# Adafruit_VS1053_Headphone_FeatherWing.net
KiCad netlist of a schematic drawn in EAGLE
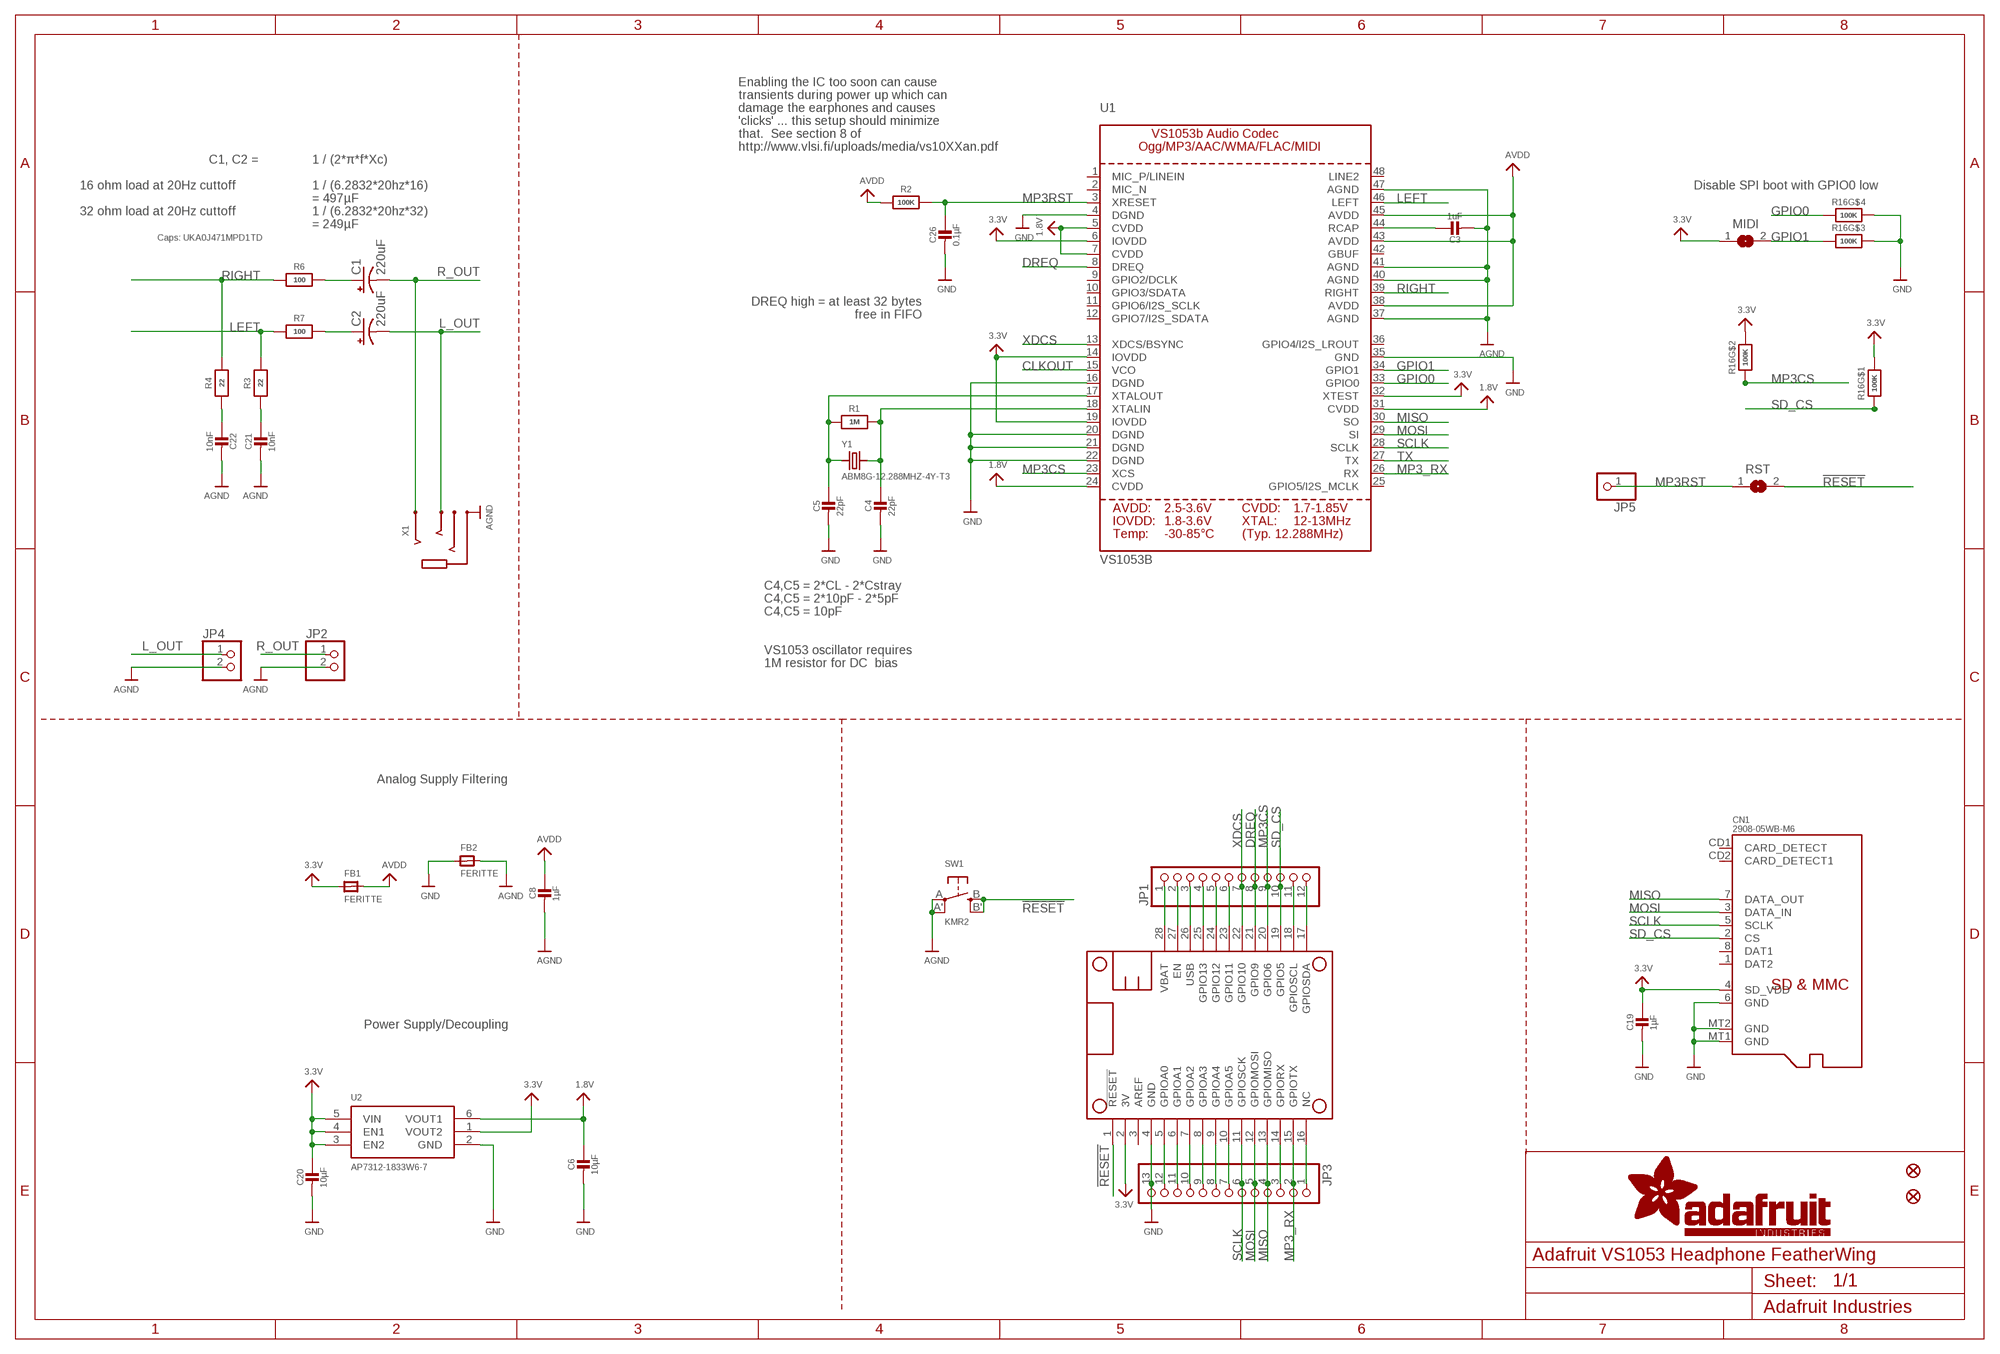
[diagram p0: schematic, sheet 1]

(export (version "E")
  (design (tool "Eeschema 10.0.6"))
  (components
    (comp (ref "C1")
      (value "220uF")
      (footprint "eagle-import:PANASONIC_C")
      (libsource (lib "eagle-import") (part "CPOL-USC"))
    )
    (comp (ref "C2")
      (value "220uF")
      (footprint "eagle-import:PANASONIC_C")
      (libsource (lib "eagle-import") (part "CPOL-USC"))
    )
    (comp (ref "C3")
      (value "1uF")
      (footprint "eagle-import:0603-NO")
      (libsource (lib "eagle-import") (part "CAP_CERAMIC0603_NO"))
    )
    (comp (ref "C4")
      (value "22pF")
      (footprint "eagle-import:0603-NO")
      (libsource (lib "eagle-import") (part "CAP_CERAMIC0603_NO"))
    )
    (comp (ref "C5")
      (value "22pF")
      (footprint "eagle-import:0603-NO")
      (libsource (lib "eagle-import") (part "CAP_CERAMIC0603_NO"))
    )
    (comp (ref "C6")
      (value "10µF")
      (footprint "eagle-import:_0805MP")
      (libsource (lib "eagle-import") (part "CAP_CERAMIC_0805MP"))
    )
    (comp (ref "C8")
      (value "1µF")
      (footprint "eagle-import:0603-NO")
      (libsource (lib "eagle-import") (part "CAP_CERAMIC0603_NO"))
    )
    (comp (ref "C19")
      (value "1µF")
      (footprint "eagle-import:0603-NO")
      (libsource (lib "eagle-import") (part "CAP_CERAMIC0603_NO"))
    )
    (comp (ref "C20")
      (value "10µF")
      (footprint "eagle-import:0805-NO")
      (libsource (lib "eagle-import") (part "CAP_CERAMIC0805-NOOUTLINE"))
    )
    (comp (ref "C21")
      (value "10nF")
      (footprint "eagle-import:0603-NO")
      (libsource (lib "eagle-import") (part "CAP_CERAMIC0603_NO"))
    )
    (comp (ref "C22")
      (value "10nF")
      (footprint "eagle-import:0603-NO")
      (libsource (lib "eagle-import") (part "CAP_CERAMIC0603_NO"))
    )
    (comp (ref "C26")
      (value "0.1µF")
      (footprint "eagle-import:0603-NO")
      (libsource (lib "eagle-import") (part "CAP_CERAMIC0603_NO"))
    )
    (comp (ref "CN1")
      (value "2908-05WB-M6")
      (footprint "eagle-import:MICROSD")
      (libsource (lib "eagle-import") (part "MICROSD"))
    )
    (comp (ref "FB1")
      (value "FERITTE")
      (footprint "eagle-import:0805-NO")
      (libsource (lib "eagle-import") (part "FERRITE-0805NO"))
    )
    (comp (ref "FB2")
      (value "FERITTE")
      (footprint "eagle-import:0805-NO")
      (libsource (lib "eagle-import") (part "FERRITE-0805NO"))
    )
    (comp (ref "FID1")
      (value "FIDUCIAL\"\"")
      (footprint "eagle-import:FIDUCIAL_1MM")
      (libsource (lib "eagle-import") (part "FIDUCIAL{dblquote}{dblquote}"))
    )
    (comp (ref "FID2")
      (value "FIDUCIAL\"\"")
      (footprint "eagle-import:FIDUCIAL_1MM")
      (libsource (lib "eagle-import") (part "FIDUCIAL{dblquote}{dblquote}"))
    )
    (comp (ref "JP1")
      (value "HEADER-1X12")
      (footprint "eagle-import:1X12_ROUND")
      (libsource (lib "eagle-import") (part "HEADER-1X12"))
    )
    (comp (ref "JP2")
      (value "HEADER-1X2ROUND")
      (footprint "eagle-import:1X02_ROUND")
      (libsource (lib "eagle-import") (part "HEADER-1X2ROUND"))
    )
    (comp (ref "JP3")
      (value "HEADER-1X13")
      (footprint "eagle-import:1X13_ROUND_70")
      (libsource (lib "eagle-import") (part "HEADER-1X13"))
    )
    (comp (ref "JP4")
      (value "HEADER-1X2ROUND")
      (footprint "eagle-import:1X02_ROUND")
      (libsource (lib "eagle-import") (part "HEADER-1X2ROUND"))
    )
    (comp (ref "JP5")
      (value "HEADER-1X1ROUND")
      (footprint "eagle-import:1X01_ROUND")
      (libsource (lib "eagle-import") (part "HEADER-1X1ROUND"))
    )
    (comp (ref "MIDI")
      (value "SOLDERJUMPER")
      (footprint "eagle-import:SOLDERJUMPER_ARROW_NOPASTE")
      (libsource (lib "eagle-import") (part "SOLDERJUMPER"))
    )
    (comp (ref "MS1")
      (value "FEATHERWING_NODIM")
      (footprint "eagle-import:FEATHERWING_NODIM")
      (libsource (lib "eagle-import") (part "FEATHERWING_NODIM"))
    )
    (comp (ref "R1")
      (value "1M")
      (footprint "eagle-import:0603-NO")
      (libsource (lib "eagle-import") (part "RESISTOR_0603_NOOUT"))
    )
    (comp (ref "R2")
      (value "100K")
      (footprint "eagle-import:0603-NO")
      (libsource (lib "eagle-import") (part "RESISTOR_0603_NOOUT"))
    )
    (comp (ref "R3")
      (value "22")
      (footprint "eagle-import:0603-NO")
      (libsource (lib "eagle-import") (part "RESISTOR_0603_NOOUT"))
    )
    (comp (ref "R4")
      (value "22")
      (footprint "eagle-import:0603-NO")
      (libsource (lib "eagle-import") (part "RESISTOR_0603_NOOUT"))
    )
    (comp (ref "R6")
      (value "100")
      (footprint "eagle-import:0603-NO")
      (libsource (lib "eagle-import") (part "RESISTOR_0603_NOOUT"))
    )
    (comp (ref "R7")
      (value "100")
      (footprint "eagle-import:0603-NO")
      (libsource (lib "eagle-import") (part "RESISTOR_0603_NOOUT"))
    )
    (comp (ref "R16")
      (value "100K")
      (footprint "eagle-import:RESPACK_4X0603")
      (libsource (lib "eagle-import") (part "RESISTOR_4PACK"))
    )
    (comp (ref "RST")
      (value "SOLDERJUMPERCLOSED")
      (footprint "eagle-import:SOLDERJUMPER_CLOSEDWIRE")
      (libsource (lib "eagle-import") (part "SOLDERJUMPERCLOSED"))
    )
    (comp (ref "SW1")
      (value "KMR2")
      (footprint "eagle-import:BTN_KMR2_4.6X2.8")
      (libsource (lib "eagle-import") (part "SWITCH_TACT_SMT4.6X2.8"))
    )
    (comp (ref "U1")
      (value "VS1053B")
      (footprint "eagle-import:LQFP48")
      (libsource (lib "eagle-import") (part "VS1053B"))
    )
    (comp (ref "U2")
      (value "AP7312-1833W6-7")
      (footprint "eagle-import:SOT23-6")
      (libsource (lib "eagle-import") (part "VREG_SOT23-6_DUALAP7312"))
    )
    (comp (ref "X1")
      (value "AUDIO_3.5MMJACK_4POL")
      (footprint "eagle-import:4UCONN_18510")
      (libsource (lib "eagle-import") (part "AUDIO_3.5MMJACK_4POL"))
    )
    (comp (ref "Y1")
      (value "ABM8G-12.288MHZ-4Y-T3")
      (footprint "eagle-import:CRYSTAL_3.2X2.5")
      (libsource (lib "eagle-import") (part "CRYSTAL3.2X2.5"))
    )
  )
  (nets
    (net (code "1") (name "/CLKOUT") (class "Default")
      (node (ref "U1") (pin "15") (pinfunction "VCO_15") (pintype "bidirectional"))
    )
    (net (code "2") (name "/DREQ") (class "Default")
      (node (ref "JP1") (pin "8") (pinfunction "8_8") (pintype "passive"))
      (node (ref "MS1") (pin "21") (pinfunction "GPIO9_21") (pintype "bidirectional"))
      (node (ref "U1") (pin "8") (pinfunction "DREQ_8") (pintype "bidirectional"))
    )
    (net (code "3") (name "/GPIO0") (class "Default")
      (node (ref "R16") (pin "4") (pinfunction "1_4") (pintype "passive"))
      (node (ref "U1") (pin "33") (pinfunction "GPIO0_33") (pintype "bidirectional"))
    )
    (net (code "4") (name "/GPIO1") (class "Default")
      (node (ref "MIDI") (pin "2") (pinfunction "2_2") (pintype "passive"))
      (node (ref "R16") (pin "3") (pinfunction "1_3") (pintype "passive"))
      (node (ref "U1") (pin "34") (pinfunction "GPIO1_34") (pintype "bidirectional"))
    )
    (net (code "5") (name "/LEFT") (class "Default")
      (node (ref "R3") (pin "1") (pinfunction "1_1") (pintype "passive"))
      (node (ref "R7") (pin "2") (pinfunction "2_2") (pintype "passive"))
      (node (ref "U1") (pin "46") (pinfunction "LEFT_46") (pintype "bidirectional"))
    )
    (net (code "6") (name "/L_OUT") (class "Default")
      (node (ref "C2") (pin "-") (pinfunction "-_-") (pintype "passive"))
      (node (ref "JP4") (pin "1") (pinfunction "1_1") (pintype "passive"))
      (node (ref "X1") (pin "2-TIP") (pinfunction "RING3_2-TIP") (pintype "passive"))
    )
    (net (code "7") (name "/MISO") (class "Default")
      (node (ref "CN1") (pin "7") (pinfunction "DATA_OUT_7") (pintype "output"))
      (node (ref "JP3") (pin "4") (pinfunction "4_4") (pintype "passive"))
      (node (ref "MS1") (pin "13") (pinfunction "GPIOMISO_13") (pintype "bidirectional"))
      (node (ref "U1") (pin "30") (pinfunction "SO_30") (pintype "bidirectional"))
    )
    (net (code "8") (name "/MOSI") (class "Default")
      (node (ref "CN1") (pin "3") (pinfunction "DATA_IN_3") (pintype "input"))
      (node (ref "JP3") (pin "5") (pinfunction "5_5") (pintype "passive"))
      (node (ref "MS1") (pin "12") (pinfunction "GPIOMOSI_12") (pintype "bidirectional"))
      (node (ref "U1") (pin "29") (pinfunction "SI_29") (pintype "bidirectional"))
    )
    (net (code "9") (name "/MP3CS") (class "Default")
      (node (ref "JP1") (pin "9") (pinfunction "9_9") (pintype "passive"))
      (node (ref "MS1") (pin "20") (pinfunction "GPIO6_20") (pintype "bidirectional"))
      (node (ref "R16") (pin "2") (pinfunction "1_2") (pintype "passive"))
      (node (ref "U1") (pin "23") (pinfunction "XCS_23") (pintype "bidirectional"))
    )
    (net (code "10") (name "/MP3RST") (class "Default")
      (node (ref "C26") (pin "1") (pinfunction "1_1") (pintype "passive"))
      (node (ref "JP5") (pin "1") (pinfunction "1_1") (pintype "passive"))
      (node (ref "R2") (pin "2") (pinfunction "2_2") (pintype "passive"))
      (node (ref "RST") (pin "1") (pinfunction "1_1") (pintype "passive"))
      (node (ref "U1") (pin "3") (pinfunction "XRESET_3") (pintype "bidirectional"))
    )
    (net (code "11") (name "/MP3_RX") (class "Default")
      (node (ref "JP3") (pin "2") (pinfunction "2_2") (pintype "passive"))
      (node (ref "MS1") (pin "15") (pinfunction "GPIOTX_15") (pintype "bidirectional"))
      (node (ref "U1") (pin "26") (pinfunction "RX_26") (pintype "bidirectional"))
    )
    (net (code "12") (name "/RIGHT") (class "Default")
      (node (ref "R4") (pin "1") (pinfunction "1_1") (pintype "passive"))
      (node (ref "R6") (pin "2") (pinfunction "2_2") (pintype "passive"))
      (node (ref "U1") (pin "39") (pinfunction "RIGHT_39") (pintype "bidirectional"))
    )
    (net (code "13") (name "/R_OUT") (class "Default")
      (node (ref "C1") (pin "-") (pinfunction "-_-") (pintype "passive"))
      (node (ref "JP2") (pin "1") (pinfunction "1_1") (pintype "passive"))
      (node (ref "X1") (pin "3-OUTER_SLEEVE") (pinfunction "RING2_3-OUTER_SLEEVE") (pintype "passive"))
    )
    (net (code "14") (name "/SCLK") (class "Default")
      (node (ref "CN1") (pin "5") (pinfunction "SCLK_5") (pintype "input"))
      (node (ref "JP3") (pin "6") (pinfunction "6_6") (pintype "passive"))
      (node (ref "MS1") (pin "11") (pinfunction "GPIOSCK_11") (pintype "bidirectional"))
      (node (ref "U1") (pin "28") (pinfunction "SCLK_28") (pintype "bidirectional"))
    )
    (net (code "15") (name "/SD_CS") (class "Default")
      (node (ref "CN1") (pin "2") (pinfunction "CS_2") (pintype "input"))
      (node (ref "JP1") (pin "10") (pinfunction "10_10") (pintype "passive"))
      (node (ref "MS1") (pin "19") (pinfunction "GPIO5_19") (pintype "bidirectional"))
      (node (ref "R16") (pin "1") (pinfunction "1_1") (pintype "passive"))
    )
    (net (code "16") (name "/TX") (class "Default")
      (node (ref "U1") (pin "27") (pinfunction "TX_27") (pintype "bidirectional"))
    )
    (net (code "17") (name "/XDCS") (class "Default")
      (node (ref "JP1") (pin "7") (pinfunction "7_7") (pintype "passive"))
      (node (ref "MS1") (pin "22") (pinfunction "GPIO10_22") (pintype "bidirectional"))
      (node (ref "U1") (pin "13") (pinfunction "XDCS/BSYNC_13") (pintype "bidirectional"))
    )
    (net (code "18") (name "/~{RESET}") (class "Default")
      (node (ref "MS1") (pin "1") (pinfunction "~{RESET}_1") (pintype "input"))
      (node (ref "RST") (pin "2") (pinfunction "2_2") (pintype "passive"))
      (node (ref "SW1") (pin "B") (pinfunction "S_B") (pintype "passive"))
      (node (ref "SW1") (pin "B'") (pinfunction "S1_B'") (pintype "passive"))
    )
    (net (code "19") (name "1.8V") (class "Default")
      (node (ref "C6") (pin "1") (pinfunction "1_1") (pintype "passive"))
      (node (ref "U1") (pin "24") (pinfunction "CVDD_24") (pintype "power_in"))
      (node (ref "U1") (pin "31") (pinfunction "CVDD_31") (pintype "power_in"))
      (node (ref "U1") (pin "5") (pinfunction "CVDD_5") (pintype "power_in"))
      (node (ref "U1") (pin "7") (pinfunction "CVDD_7") (pintype "power_in"))
      (node (ref "U2") (pin "6") (pinfunction "VOUT1_6") (pintype "bidirectional"))
    )
    (net (code "20") (name "3.3V") (class "Default")
      (node (ref "C19") (pin "1") (pinfunction "1_1") (pintype "passive"))
      (node (ref "C20") (pin "1") (pinfunction "1_1") (pintype "passive"))
      (node (ref "CN1") (pin "4") (pinfunction "SD_VDD_4") (pintype "power_in"))
      (node (ref "FB1") (pin "1") (pinfunction "P$1_1") (pintype "passive"))
      (node (ref "MIDI") (pin "1") (pinfunction "1_1") (pintype "passive"))
      (node (ref "MS1") (pin "2") (pinfunction "3V_2") (pintype "power_in"))
      (node (ref "R16") (pin "7") (pinfunction "2_7") (pintype "passive"))
      (node (ref "R16") (pin "8") (pinfunction "2_8") (pintype "passive"))
      (node (ref "U1") (pin "14") (pinfunction "IOVDD_14") (pintype "power_in"))
      (node (ref "U1") (pin "19") (pinfunction "IOVDD_19") (pintype "power_in"))
      (node (ref "U1") (pin "32") (pinfunction "XTEST_32") (pintype "bidirectional"))
      (node (ref "U1") (pin "6") (pinfunction "IOVDD_6") (pintype "power_in"))
      (node (ref "U2") (pin "1") (pinfunction "VOUT2_1") (pintype "bidirectional"))
      (node (ref "U2") (pin "3") (pinfunction "EN2_3") (pintype "bidirectional"))
      (node (ref "U2") (pin "4") (pinfunction "EN1_4") (pintype "bidirectional"))
      (node (ref "U2") (pin "5") (pinfunction "VIN_5") (pintype "bidirectional"))
    )
    (net (code "21") (name "AGND") (class "Default")
      (node (ref "C21") (pin "2") (pinfunction "2_2") (pintype "passive"))
      (node (ref "C22") (pin "2") (pinfunction "2_2") (pintype "passive"))
      (node (ref "C3") (pin "2") (pinfunction "2_2") (pintype "passive"))
      (node (ref "C8") (pin "2") (pinfunction "2_2") (pintype "passive"))
      (node (ref "FB2") (pin "2") (pinfunction "P$2_2") (pintype "passive"))
      (node (ref "JP2") (pin "2") (pinfunction "2_2") (pintype "passive"))
      (node (ref "JP4") (pin "2") (pinfunction "2_2") (pintype "passive"))
      (node (ref "SW1") (pin "A") (pinfunction "P_A") (pintype "passive"))
      (node (ref "SW1") (pin "A'") (pinfunction "P1_A'") (pintype "passive"))
      (node (ref "U1") (pin "37") (pinfunction "AGND_37") (pintype "power_in"))
      (node (ref "U1") (pin "40") (pinfunction "AGND_40") (pintype "power_in"))
      (node (ref "U1") (pin "41") (pinfunction "AGND_41") (pintype "power_in"))
      (node (ref "U1") (pin "47") (pinfunction "AGND_47") (pintype "power_in"))
      (node (ref "X1") (pin "1-GND") (pinfunction "TIP_1-GND") (pintype "passive"))
    )
    (net (code "22") (name "AVDD") (class "Default")
      (node (ref "C8") (pin "1") (pinfunction "1_1") (pintype "passive"))
      (node (ref "FB1") (pin "2") (pinfunction "P$2_2") (pintype "passive"))
      (node (ref "R2") (pin "1") (pinfunction "1_1") (pintype "passive"))
      (node (ref "U1") (pin "38") (pinfunction "AVDD_38") (pintype "power_in"))
      (node (ref "U1") (pin "43") (pinfunction "AVDD_43") (pintype "power_in"))
      (node (ref "U1") (pin "45") (pinfunction "AVDD_45") (pintype "power_in"))
    )
    (net (code "23") (name "GND") (class "Default")
      (node (ref "C19") (pin "2") (pinfunction "2_2") (pintype "passive"))
      (node (ref "C20") (pin "2") (pinfunction "2_2") (pintype "passive"))
      (node (ref "C26") (pin "2") (pinfunction "2_2") (pintype "passive"))
      (node (ref "C4") (pin "2") (pinfunction "2_2") (pintype "passive"))
      (node (ref "C5") (pin "2") (pinfunction "2_2") (pintype "passive"))
      (node (ref "C6") (pin "2") (pinfunction "2_2") (pintype "passive"))
      (node (ref "CN1") (pin "6") (pinfunction "GND_6") (pintype "power_in"))
      (node (ref "CN1") (pin "MT1") (pinfunction "GND_MT1") (pintype "power_in"))
      (node (ref "CN1") (pin "MT2") (pinfunction "GND_MT2") (pintype "power_in"))
      (node (ref "FB2") (pin "1") (pinfunction "P$1_1") (pintype "passive"))
      (node (ref "JP3") (pin "13") (pinfunction "13_13") (pintype "passive"))
      (node (ref "MS1") (pin "4") (pinfunction "GND_4") (pintype "power_in"))
      (node (ref "R16") (pin "5") (pinfunction "2_5") (pintype "passive"))
      (node (ref "R16") (pin "6") (pinfunction "2_6") (pintype "passive"))
      (node (ref "U1") (pin "16") (pinfunction "DGND_16") (pintype "power_in"))
      (node (ref "U1") (pin "20") (pinfunction "DGND_20") (pintype "power_in"))
      (node (ref "U1") (pin "21") (pinfunction "DGND_21") (pintype "power_in"))
      (node (ref "U1") (pin "22") (pinfunction "DGND_22") (pintype "power_in"))
      (node (ref "U1") (pin "35") (pinfunction "GND_35") (pintype "power_in"))
      (node (ref "U1") (pin "4") (pinfunction "DGND_4") (pintype "power_in"))
      (node (ref "U2") (pin "2") (pinfunction "GND_2") (pintype "bidirectional"))
    )
    (net (code "24") (name "Net-(C1-Pad+)") (class "Default")
      (node (ref "C1") (pin "+") (pinfunction "+_+") (pintype "passive"))
      (node (ref "R6") (pin "1") (pinfunction "1_1") (pintype "passive"))
    )
    (net (code "25") (name "Net-(C2-Pad+)") (class "Default")
      (node (ref "C2") (pin "+") (pinfunction "+_+") (pintype "passive"))
      (node (ref "R7") (pin "1") (pinfunction "1_1") (pintype "passive"))
    )
    (net (code "26") (name "Net-(C21-Pad1)") (class "Default")
      (node (ref "C21") (pin "1") (pinfunction "1_1") (pintype "passive"))
      (node (ref "R3") (pin "2") (pinfunction "2_2") (pintype "passive"))
    )
    (net (code "27") (name "Net-(C22-Pad1)") (class "Default")
      (node (ref "C22") (pin "1") (pinfunction "1_1") (pintype "passive"))
      (node (ref "R4") (pin "2") (pinfunction "2_2") (pintype "passive"))
    )
    (net (code "28") (name "Net-(MS1-EN)") (class "Default")
      (node (ref "JP1") (pin "2") (pinfunction "2_2") (pintype "passive"))
      (node (ref "MS1") (pin "27") (pinfunction "EN_27") (pintype "passive"))
    )
    (net (code "29") (name "Net-(MS1-GPIO11)") (class "Default")
      (node (ref "JP1") (pin "6") (pinfunction "6_6") (pintype "passive"))
      (node (ref "MS1") (pin "23") (pinfunction "GPIO11_23") (pintype "bidirectional"))
    )
    (net (code "30") (name "Net-(MS1-GPIO12)") (class "Default")
      (node (ref "JP1") (pin "5") (pinfunction "5_5") (pintype "passive"))
      (node (ref "MS1") (pin "24") (pinfunction "GPIO12_24") (pintype "bidirectional"))
    )
    (net (code "31") (name "Net-(MS1-GPIO13)") (class "Default")
      (node (ref "JP1") (pin "4") (pinfunction "4_4") (pintype "passive"))
      (node (ref "MS1") (pin "25") (pinfunction "GPIO13_25") (pintype "bidirectional"))
    )
    (net (code "32") (name "Net-(MS1-GPIOA0)") (class "Default")
      (node (ref "JP3") (pin "12") (pinfunction "12_12") (pintype "passive"))
      (node (ref "MS1") (pin "5") (pinfunction "GPIOA0_5") (pintype "bidirectional"))
    )
    (net (code "33") (name "Net-(MS1-GPIOA1)") (class "Default")
      (node (ref "JP3") (pin "11") (pinfunction "11_11") (pintype "passive"))
      (node (ref "MS1") (pin "6") (pinfunction "GPIOA1_6") (pintype "bidirectional"))
    )
    (net (code "34") (name "Net-(MS1-GPIOA2)") (class "Default")
      (node (ref "JP3") (pin "10") (pinfunction "10_10") (pintype "passive"))
      (node (ref "MS1") (pin "7") (pinfunction "GPIOA2_7") (pintype "bidirectional"))
    )
    (net (code "35") (name "Net-(MS1-GPIOA3)") (class "Default")
      (node (ref "JP3") (pin "9") (pinfunction "9_9") (pintype "passive"))
      (node (ref "MS1") (pin "8") (pinfunction "GPIOA3_8") (pintype "bidirectional"))
    )
    (net (code "36") (name "Net-(MS1-GPIOA4)") (class "Default")
      (node (ref "JP3") (pin "8") (pinfunction "8_8") (pintype "passive"))
      (node (ref "MS1") (pin "9") (pinfunction "GPIOA4_9") (pintype "bidirectional"))
    )
    (net (code "37") (name "Net-(MS1-GPIOA5)") (class "Default")
      (node (ref "JP3") (pin "7") (pinfunction "7_7") (pintype "passive"))
      (node (ref "MS1") (pin "10") (pinfunction "GPIOA5_10") (pintype "bidirectional"))
    )
    (net (code "38") (name "Net-(MS1-GPIORX)") (class "Default")
      (node (ref "JP3") (pin "3") (pinfunction "3_3") (pintype "passive"))
      (node (ref "MS1") (pin "14") (pinfunction "GPIORX_14") (pintype "bidirectional"))
    )
    (net (code "39") (name "Net-(MS1-GPIOSCL)") (class "Default")
      (node (ref "JP1") (pin "11") (pinfunction "11_11") (pintype "passive"))
      (node (ref "MS1") (pin "18") (pinfunction "GPIOSCL_18") (pintype "bidirectional"))
    )
    (net (code "40") (name "Net-(MS1-GPIOSDA)") (class "Default")
      (node (ref "JP1") (pin "12") (pinfunction "12_12") (pintype "passive"))
      (node (ref "MS1") (pin "17") (pinfunction "GPIOSDA_17") (pintype "bidirectional"))
    )
    (net (code "41") (name "Net-(MS1-NC)") (class "Default")
      (node (ref "JP3") (pin "1") (pinfunction "1_1") (pintype "passive"))
      (node (ref "MS1") (pin "16") (pinfunction "NC_16") (pintype "passive"))
    )
    (net (code "42") (name "Net-(MS1-USB)") (class "Default")
      (node (ref "JP1") (pin "3") (pinfunction "3_3") (pintype "passive"))
      (node (ref "MS1") (pin "26") (pinfunction "USB_26") (pintype "power_in"))
    )
    (net (code "43") (name "Net-(MS1-VBAT)") (class "Default")
      (node (ref "JP1") (pin "1") (pinfunction "1_1") (pintype "passive"))
      (node (ref "MS1") (pin "28") (pinfunction "VBAT_28") (pintype "power_in"))
    )
    (net (code "44") (name "Net-(U1-RCAP)") (class "Default")
      (node (ref "C3") (pin "1") (pinfunction "1_1") (pintype "passive"))
      (node (ref "U1") (pin "44") (pinfunction "RCAP_44") (pintype "bidirectional"))
    )
    (net (code "45") (name "Net-(U1-XTALIN)") (class "Default")
      (node (ref "C4") (pin "1") (pinfunction "1_1") (pintype "passive"))
      (node (ref "R1") (pin "2") (pinfunction "2_2") (pintype "passive"))
      (node (ref "U1") (pin "18") (pinfunction "XTALIN_18") (pintype "input"))
      (node (ref "Y1") (pin "2") (pinfunction "2_2") (pintype "passive"))
    )
    (net (code "46") (name "Net-(U1-XTALOUT)") (class "Default")
      (node (ref "C5") (pin "1") (pinfunction "1_1") (pintype "passive"))
      (node (ref "R1") (pin "1") (pinfunction "1_1") (pintype "passive"))
      (node (ref "U1") (pin "17") (pinfunction "XTALOUT_17") (pintype "output"))
      (node (ref "Y1") (pin "1") (pinfunction "1_1") (pintype "passive"))
    )
    (net (code "47") (name "unconnected-(CN1-CARD_DETECT-PadCD1)") (class "Default")
      (node (ref "CN1") (pin "CD1") (pinfunction "CARD_DETECT_CD1") (pintype "passive"))
    )
    (net (code "48") (name "unconnected-(CN1-CARD_DETECT1-PadCD2)") (class "Default")
      (node (ref "CN1") (pin "CD2") (pinfunction "CARD_DETECT1_CD2") (pintype "passive"))
    )
    (net (code "49") (name "unconnected-(CN1-DAT1-Pad8)") (class "Default")
      (node (ref "CN1") (pin "8") (pinfunction "DAT1_8") (pintype "bidirectional"))
    )
    (net (code "50") (name "unconnected-(CN1-DAT2-Pad1)") (class "Default")
      (node (ref "CN1") (pin "1") (pinfunction "DAT2_1") (pintype "bidirectional"))
    )
    (net (code "51") (name "unconnected-(MS1-AREF-Pad3)") (class "Default")
      (node (ref "MS1") (pin "3") (pinfunction "AREF_3") (pintype "passive"))
    )
    (net (code "52") (name "unconnected-(U1-GBUF-Pad42)") (class "Default")
      (node (ref "U1") (pin "42") (pinfunction "GBUF_42") (pintype "bidirectional"))
    )
    (net (code "53") (name "unconnected-(U1-GPIO2{slash}DCLK-Pad9)") (class "Default")
      (node (ref "U1") (pin "9") (pinfunction "GPIO2/DCLK_9") (pintype "bidirectional"))
    )
    (net (code "54") (name "unconnected-(U1-GPIO3{slash}SDATA-Pad10)") (class "Default")
      (node (ref "U1") (pin "10") (pinfunction "GPIO3/SDATA_10") (pintype "bidirectional"))
    )
    (net (code "55") (name "unconnected-(U1-GPIO4{slash}I2S_LROUT-Pad36)") (class "Default")
      (node (ref "U1") (pin "36") (pinfunction "GPIO4/I2S_LROUT_36") (pintype "bidirectional"))
    )
    (net (code "56") (name "unconnected-(U1-GPIO5{slash}I2S_MCLK-Pad25)") (class "Default")
      (node (ref "U1") (pin "25") (pinfunction "GPIO5/I2S_MCLK_25") (pintype "bidirectional"))
    )
    (net (code "57") (name "unconnected-(U1-GPIO6{slash}I2S_SCLK-Pad11)") (class "Default")
      (node (ref "U1") (pin "11") (pinfunction "GPIO6/I2S_SCLK_11") (pintype "bidirectional"))
    )
    (net (code "58") (name "unconnected-(U1-GPIO7{slash}I2S_SDATA-Pad12)") (class "Default")
      (node (ref "U1") (pin "12") (pinfunction "GPIO7/I2S_SDATA_12") (pintype "bidirectional"))
    )
    (net (code "59") (name "unconnected-(U1-LINE2-Pad48)") (class "Default")
      (node (ref "U1") (pin "48") (pinfunction "LINE2_48") (pintype "bidirectional"))
    )
    (net (code "60") (name "unconnected-(U1-MIC_N-Pad2)") (class "Default")
      (node (ref "U1") (pin "2") (pinfunction "MIC_N_2") (pintype "bidirectional"))
    )
    (net (code "61") (name "unconnected-(U1-MIC_P{slash}LINEIN-Pad1)") (class "Default")
      (node (ref "U1") (pin "1") (pinfunction "MIC_P/LINEIN_1") (pintype "bidirectional"))
    )
    (net (code "62") (name "unconnected-(X1-RING1-Pad4-INNER_SLEEVE)") (class "Default")
      (node (ref "X1") (pin "4-INNER_SLEEVE") (pinfunction "RING1_4-INNER_SLEEVE") (pintype "passive"))
    )
  )
)
